# CufflessPTT-_v3.net
KiCad netlist of a schematic drawn in EAGLE
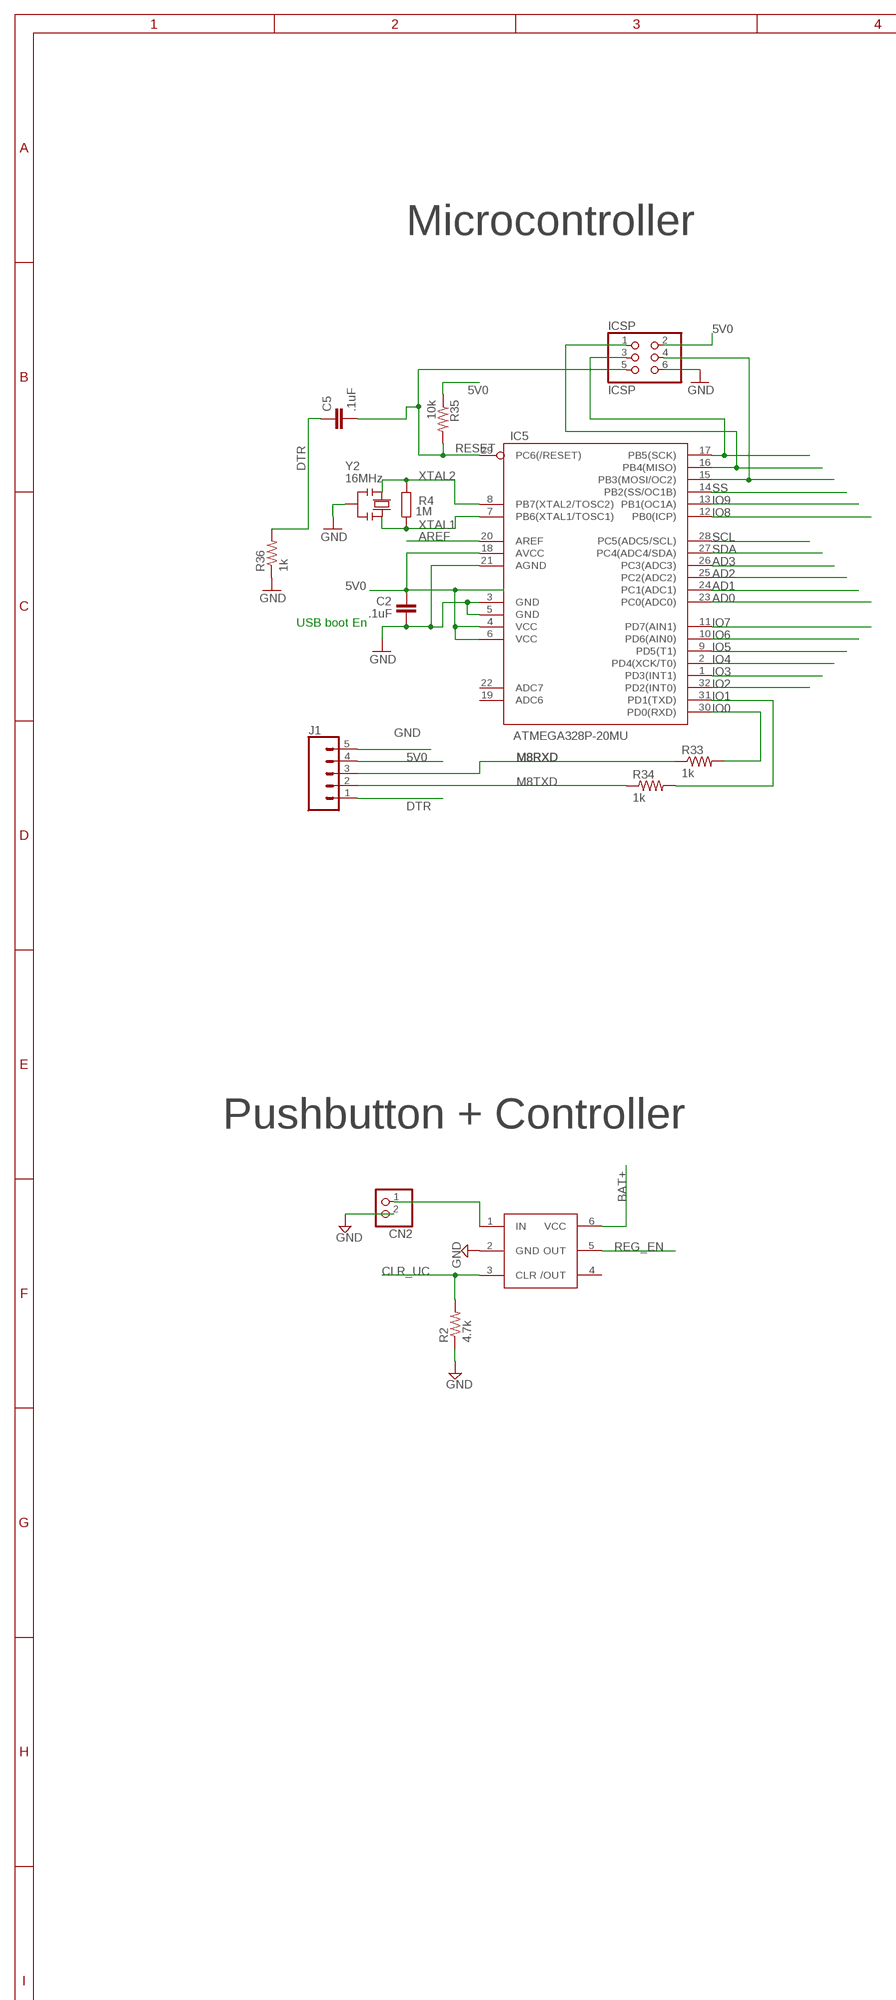
[diagram p0: schematic, sheet 1, part 1 of 2]
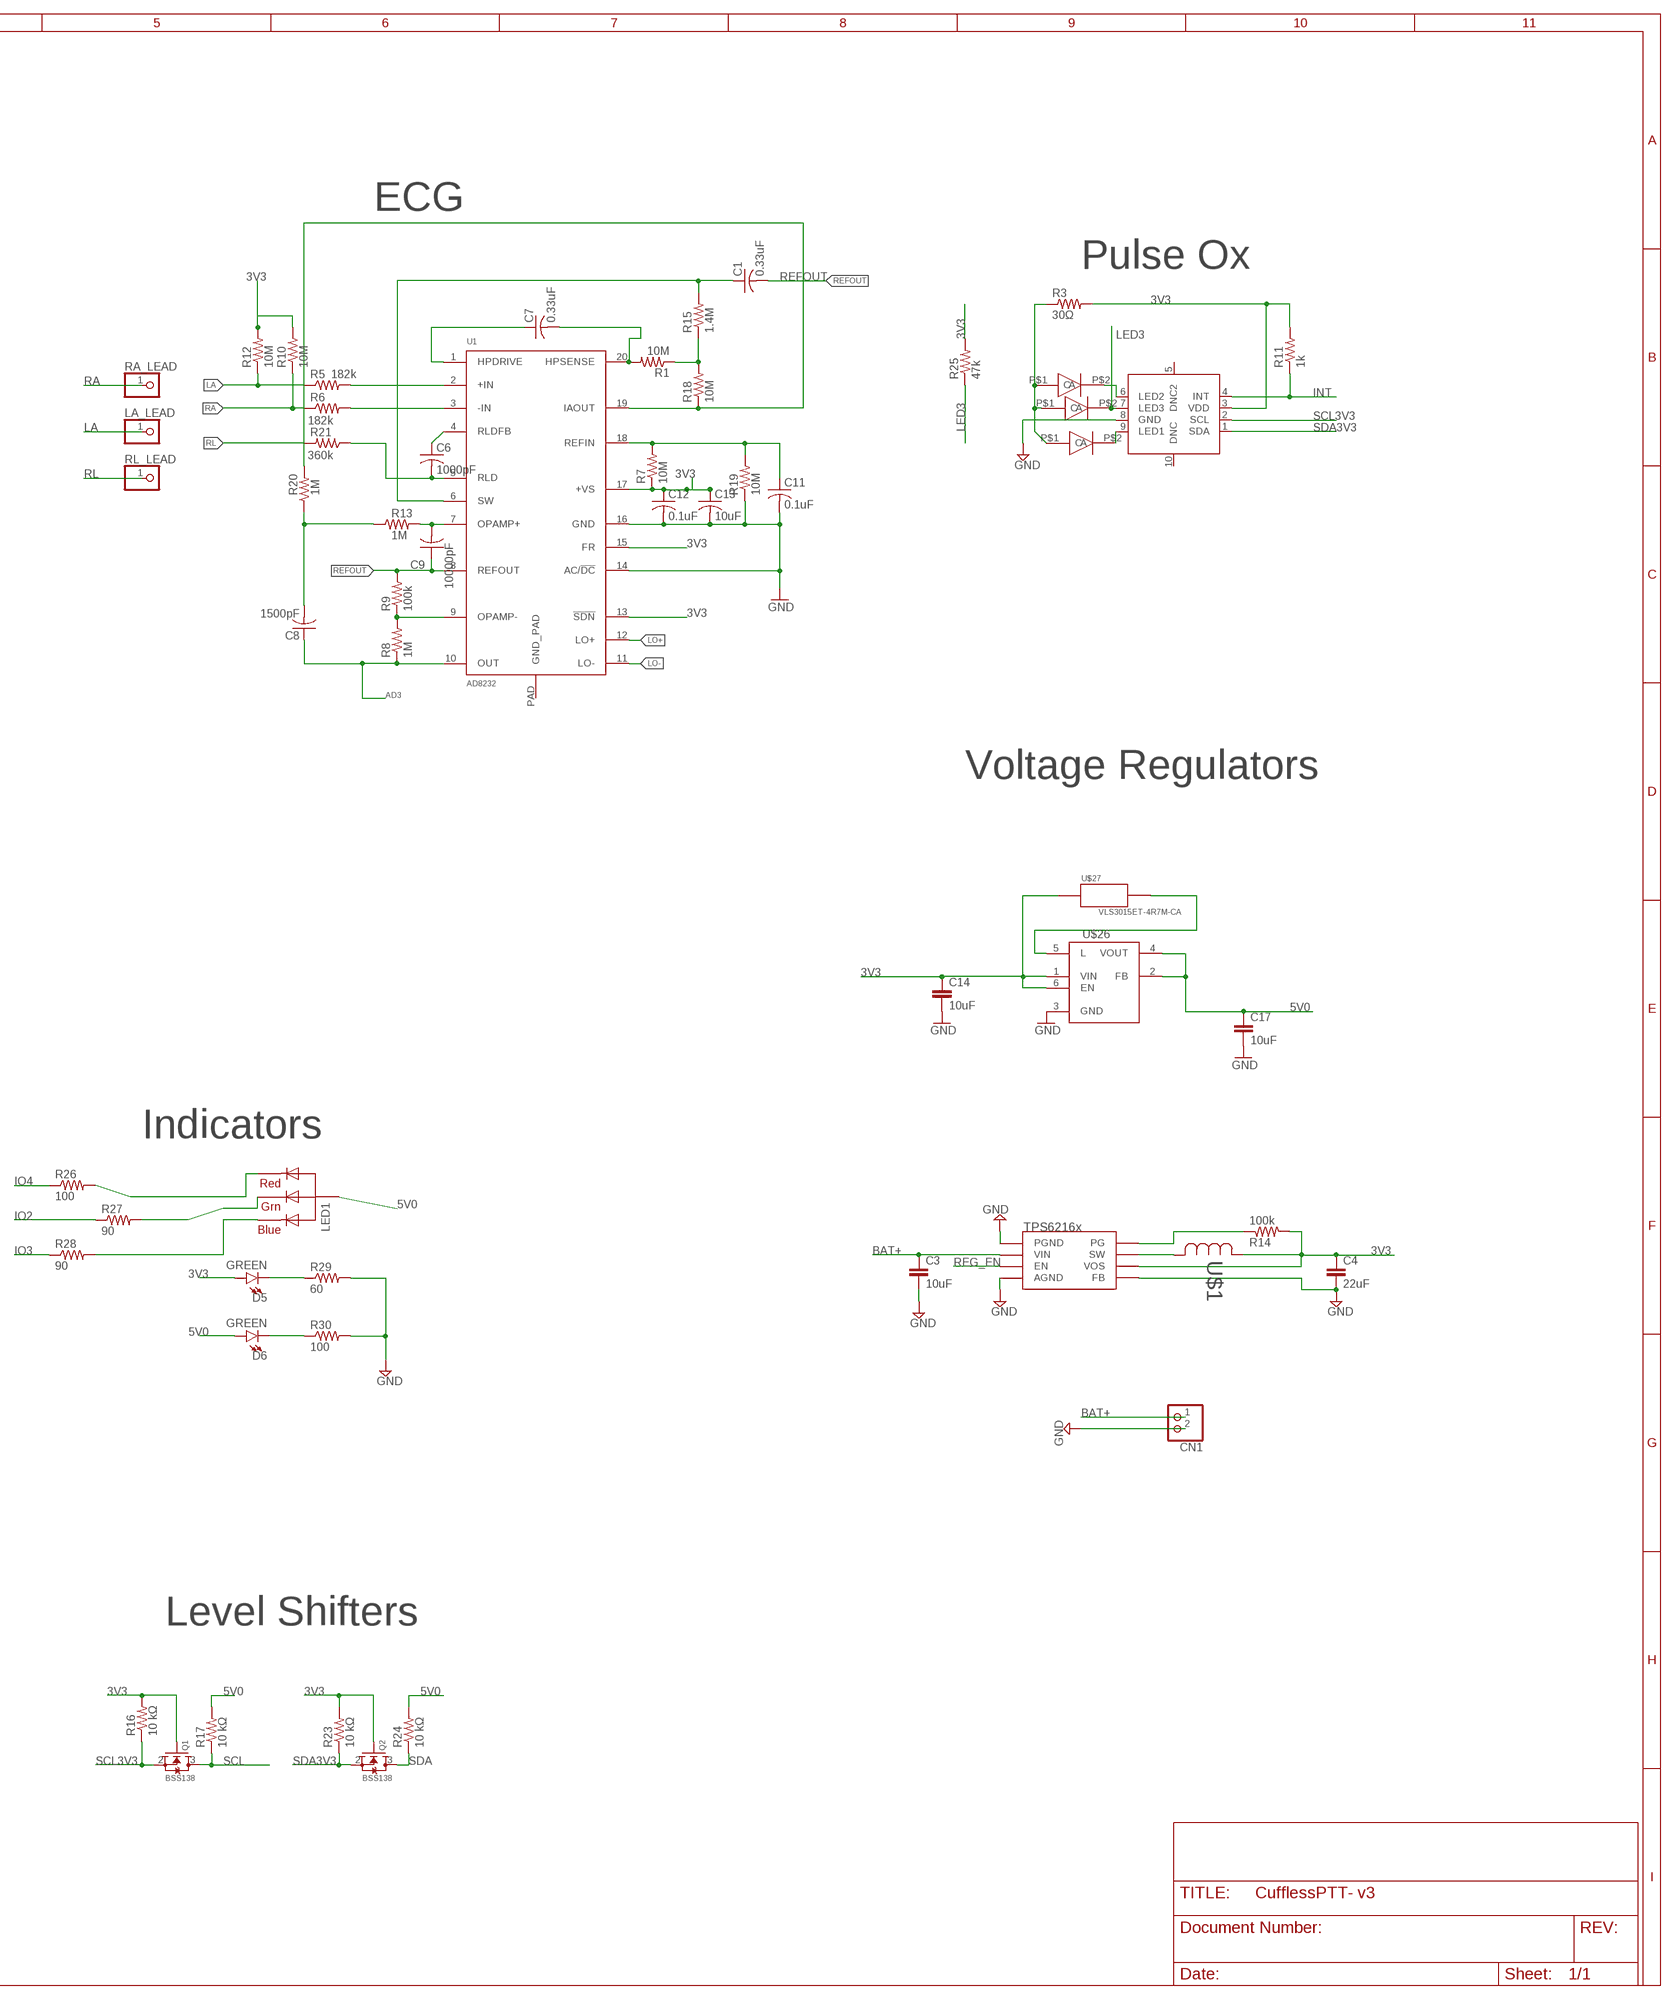
[diagram p1: schematic, sheet 1, part 2 of 2]

(export (version "E")
  (design (tool "Eeschema 10.0.6"))
  (components
    (comp (ref "C1")
      (value "0.33uF")
      (footprint "eagle-import:C0603")
      (libsource (lib "eagle-import") (part "C-USC0603"))
    )
    (comp (ref "C2")
      (value ".1uF")
      (footprint "eagle-import:C0603-ROUND")
      (libsource (lib "eagle-import") (part "C-EU0603-RND"))
    )
    (comp (ref "C3")
      (value "10uF")
      (footprint "eagle-import:C0603")
      (fields (field (name "MPN") "MCNP16V105M5X11"))
      (libsource (lib "eagle-import") (part "rcl_334_C-EUC0603"))
    )
    (comp (ref "C4")
      (value "22uF")
      (footprint "eagle-import:C0805")
      (libsource (lib "eagle-import") (part "rcl_334_C-EUC0805"))
    )
    (comp (ref "C5")
      (value ".1uF")
      (footprint "eagle-import:C0603-ROUND")
      (libsource (lib "eagle-import") (part "C-EU0603-RND"))
    )
    (comp (ref "C6")
      (value "1000pF")
      (footprint "eagle-import:C0603")
      (libsource (lib "eagle-import") (part "C-USC0603"))
    )
    (comp (ref "C7")
      (value "0.33uF")
      (footprint "eagle-import:C0603")
      (libsource (lib "eagle-import") (part "C-USC0603"))
    )
    (comp (ref "C8")
      (value "1500pF")
      (footprint "eagle-import:C0603")
      (libsource (lib "eagle-import") (part "C-USC0603"))
    )
    (comp (ref "C9")
      (value "10000pF")
      (footprint "eagle-import:C0603")
      (libsource (lib "eagle-import") (part "C-USC0603"))
    )
    (comp (ref "C11")
      (value "0.1uF")
      (footprint "eagle-import:C0603")
      (libsource (lib "eagle-import") (part "C-USC0603"))
    )
    (comp (ref "C12")
      (value "0.1uF")
      (footprint "eagle-import:C0603")
      (libsource (lib "eagle-import") (part "C-USC0603"))
    )
    (comp (ref "C13")
      (value "10uF")
      (footprint "eagle-import:C0603")
      (libsource (lib "eagle-import") (part "C-USC0603"))
    )
    (comp (ref "C14")
      (value "10uF")
      (footprint "eagle-import:C0603")
      (fields (field (name "MPN") "MCNP16V105M5X11"))
      (libsource (lib "eagle-import") (part "rcl_334_C-EUC0603"))
    )
    (comp (ref "C17")
      (value "10uF")
      (footprint "eagle-import:C0603")
      (fields (field (name "MPN") "MCNP16V105M5X11"))
      (libsource (lib "eagle-import") (part "rcl_334_C-EUC0603"))
    )
    (comp (ref "CN1")
      (value "JST_2PIN-THM")
      (footprint "eagle-import:JST-PH-2-THM")
      (libsource (lib "eagle-import") (part "JST_2PIN-THM"))
    )
    (comp (ref "CN2")
      (value "JST_2PIN-THM")
      (footprint "eagle-import:JST-PH-2-THM")
      (libsource (lib "eagle-import") (part "JST_2PIN-THM"))
    )
    (comp (ref "D5")
      (value "GREEN")
      (footprint "eagle-import:LED-0603")
      (libsource (lib "eagle-import") (part "LED-GREEN0603"))
    )
    (comp (ref "D6")
      (value "GREEN")
      (footprint "eagle-import:LED-0603")
      (libsource (lib "eagle-import") (part "LED-GREEN0603"))
    )
    (comp (ref "IC5")
      (value "ATMEGA328P-20MU")
      (footprint "eagle-import:MLF32")
      (libsource (lib "eagle-import") (part "MEGA8-MI"))
    )
    (comp (ref "ICSP")
      (value "ICSP")
      (footprint "eagle-import:2X03")
      (libsource (lib "eagle-import") (part "PINHD-2X3"))
    )
    (comp (ref "J1")
      (value "CONN_05")
      (footprint "eagle-import:1X05")
      (libsource (lib "eagle-import") (part "CONN_05"))
    )
    (comp (ref "LA_LEAD")
      (value "PINHD-1X1")
      (footprint "eagle-import:1X01")
      (libsource (lib "eagle-import") (part "PINHD-1X1"))
    )
    (comp (ref "LED1")
      (value "RGBLED_CA-5MM")
      (footprint "eagle-import:LED5MMRGB")
      (libsource (lib "eagle-import") (part "RGBLED_CA-5MM"))
    )
    (comp (ref "LED2")
      (value "SMD_COMBO")
      (footprint "eagle-import:SMD_COMBO")
      (libsource (lib "eagle-import") (part "SMD_COMBO"))
    )
    (comp (ref "LED3")
      (value "SMD_COMBO")
      (footprint "eagle-import:SMD_COMBO")
      (libsource (lib "eagle-import") (part "SMD_COMBO"))
    )
    (comp (ref "LED4")
      (value "SMD_COMBO")
      (footprint "eagle-import:SMD_COMBO")
      (libsource (lib "eagle-import") (part "SMD_COMBO"))
    )
    (comp (ref "Q1")
      (value "BSS138")
      (footprint "eagle-import:SOT23-3")
      (libsource (lib "eagle-import") (part "BSS138"))
    )
    (comp (ref "Q2")
      (value "BSS138")
      (footprint "eagle-import:SOT23-3")
      (libsource (lib "eagle-import") (part "BSS138"))
    )
    (comp (ref "R1")
      (value "10M")
      (footprint "eagle-import:0603-RES")
      (libsource (lib "eagle-import") (part "RESISTOR0603-RES"))
    )
    (comp (ref "R2")
      (value "4.7k")
      (footprint "eagle-import:R0402")
      (libsource (lib "eagle-import") (part "R-US_R0402"))
    )
    (comp (ref "R3")
      (value "30Ω")
      (footprint "eagle-import:R0402")
      (libsource (lib "eagle-import") (part "R-US_R0402"))
    )
    (comp (ref "R4")
      (value "1M")
      (footprint "eagle-import:R0603-ROUND")
      (libsource (lib "eagle-import") (part "R-EU_R0603"))
    )
    (comp (ref "R5")
      (value "182k")
      (footprint "eagle-import:0603-RES")
      (libsource (lib "eagle-import") (part "RESISTOR0603-RES"))
    )
    (comp (ref "R6")
      (value "182k")
      (footprint "eagle-import:0603-RES")
      (libsource (lib "eagle-import") (part "RESISTOR0603-RES"))
    )
    (comp (ref "R7")
      (value "10M")
      (footprint "eagle-import:0603-RES")
      (libsource (lib "eagle-import") (part "RESISTOR0603-RES"))
    )
    (comp (ref "R8")
      (value "1M")
      (footprint "eagle-import:0603-RES")
      (libsource (lib "eagle-import") (part "RESISTOR0603-RES"))
    )
    (comp (ref "R9")
      (value "100k")
      (footprint "eagle-import:0603-RES")
      (libsource (lib "eagle-import") (part "RESISTOR0603-RES"))
    )
    (comp (ref "R10")
      (value "10M")
      (footprint "eagle-import:0603-RES")
      (libsource (lib "eagle-import") (part "RESISTOR0603-RES"))
    )
    (comp (ref "R11")
      (value "1k")
      (footprint "eagle-import:R0402")
      (libsource (lib "eagle-import") (part "R-US_R0402"))
    )
    (comp (ref "R12")
      (value "10M")
      (footprint "eagle-import:0603-RES")
      (libsource (lib "eagle-import") (part "RESISTOR0603-RES"))
    )
    (comp (ref "R13")
      (value "1M")
      (footprint "eagle-import:0603-RES")
      (libsource (lib "eagle-import") (part "RESISTOR0603-RES"))
    )
    (comp (ref "R14")
      (value "100k")
      (footprint "eagle-import:R0402")
      (libsource (lib "eagle-import") (part "rcl_334_R-US_R0402"))
    )
    (comp (ref "R15")
      (value "1.4M")
      (footprint "eagle-import:0603-RES")
      (libsource (lib "eagle-import") (part "RESISTOR0603-RES"))
    )
    (comp (ref "R16")
      (value "10 kΩ")
      (footprint "eagle-import:R0402")
      (libsource (lib "eagle-import") (part "rcl_334_R-US_R0402"))
    )
    (comp (ref "R17")
      (value "10 kΩ")
      (footprint "eagle-import:R0402")
      (libsource (lib "eagle-import") (part "rcl_334_R-US_R0402"))
    )
    (comp (ref "R18")
      (value "10M")
      (footprint "eagle-import:0603-RES")
      (libsource (lib "eagle-import") (part "RESISTOR0603-RES"))
    )
    (comp (ref "R19")
      (value "10M")
      (footprint "eagle-import:0603-RES")
      (libsource (lib "eagle-import") (part "RESISTOR0603-RES"))
    )
    (comp (ref "R20")
      (value "1M")
      (footprint "eagle-import:0603-RES")
      (libsource (lib "eagle-import") (part "RESISTOR0603-RES"))
    )
    (comp (ref "R21")
      (value "360k")
      (footprint "eagle-import:0603-RES")
      (libsource (lib "eagle-import") (part "RESISTOR0603-RES"))
    )
    (comp (ref "R23")
      (value "10 kΩ")
      (footprint "eagle-import:R0402")
      (libsource (lib "eagle-import") (part "rcl_334_R-US_R0402"))
    )
    (comp (ref "R24")
      (value "10 kΩ")
      (footprint "eagle-import:R0402")
      (libsource (lib "eagle-import") (part "rcl_334_R-US_R0402"))
    )
    (comp (ref "R25")
      (value "47k")
      (footprint "eagle-import:R0402")
      (libsource (lib "eagle-import") (part "R-US_R0402"))
    )
    (comp (ref "R26")
      (value "100")
      (footprint "eagle-import:R0402")
      (libsource (lib "eagle-import") (part "resistor_348_R-US_R0402"))
    )
    (comp (ref "R27")
      (value "90")
      (footprint "eagle-import:R0402")
      (libsource (lib "eagle-import") (part "resistor_348_R-US_R0402"))
    )
    (comp (ref "R28")
      (value "90")
      (footprint "eagle-import:R0402")
      (libsource (lib "eagle-import") (part "resistor_348_R-US_R0402"))
    )
    (comp (ref "R29")
      (value "60")
      (footprint "eagle-import:R0402")
      (libsource (lib "eagle-import") (part "resistor_348_R-US_R0402"))
    )
    (comp (ref "R30")
      (value "100")
      (footprint "eagle-import:R0402")
      (libsource (lib "eagle-import") (part "resistor_348_R-US_R0402"))
    )
    (comp (ref "R33")
      (value "1k")
      (footprint "eagle-import:R0402")
      (libsource (lib "eagle-import") (part "rcl_334_R-US_R0402"))
    )
    (comp (ref "R34")
      (value "1k")
      (footprint "eagle-import:R0402")
      (libsource (lib "eagle-import") (part "rcl_334_R-US_R0402"))
    )
    (comp (ref "R35")
      (value "10k")
      (footprint "eagle-import:R0402")
      (libsource (lib "eagle-import") (part "rcl_334_R-US_R0402"))
    )
    (comp (ref "R36")
      (value "1k")
      (footprint "eagle-import:R0402")
      (libsource (lib "eagle-import") (part "rcl_334_R-US_R0402"))
    )
    (comp (ref "RA_LEAD")
      (value "PINHD-1X1")
      (footprint "eagle-import:1X01")
      (libsource (lib "eagle-import") (part "PINHD-1X1"))
    )
    (comp (ref "RL_LEAD")
      (value "PINHD-1X1")
      (footprint "eagle-import:1X01")
      (libsource (lib "eagle-import") (part "PINHD-1X1"))
    )
    (comp (ref "U$1")
      (value "VLF3012ST-2R2M1R4")
      (footprint "eagle-import:IND_3010")
      (libsource (lib "eagle-import") (part "VLF3012ST-2R2M1R4"))
    )
    (comp (ref "U$4")
      (value "SI1143")
      (footprint "eagle-import:QFN-10")
      (libsource (lib "eagle-import") (part "SI1143"))
    )
    (comp (ref "U$5")
      (value "TPS6216X")
      (footprint "eagle-import:8WSON")
      (libsource (lib "eagle-import") (part "TPS6216X"))
    )
    (comp (ref "U$15")
      (value "MAX16054")
      (footprint "eagle-import:TSOT23-6")
      (libsource (lib "eagle-import") (part "MAX16054"))
    )
    (comp (ref "U$26")
      (value "TPS61222")
      (footprint "eagle-import:SOT363_6SOIC")
      (libsource (lib "eagle-import") (part "TPS61222"))
    )
    (comp (ref "U$27")
      (value "VLS3015ET-4R7M-CA")
      (footprint "eagle-import:VLS3015ET-4R7M-CA")
      (libsource (lib "eagle-import") (part "VLS3015ET-4R7M-CA"))
    )
    (comp (ref "U1")
      (value "AD8232")
      (footprint "eagle-import:LFCSP_20")
      (libsource (lib "eagle-import") (part "AD8232"))
    )
    (comp (ref "Y2")
      (value "16MHz")
      (footprint "eagle-import:RESONATOR")
      (libsource (lib "eagle-import") (part "RESONATORMU"))
    )
  )
  (nets
    (net (code "1") (name "/3V3") (class "Default")
      (node (ref "C12") (pin "1") (pinfunction "1_1") (pintype "passive"))
      (node (ref "C13") (pin "1") (pinfunction "1_1") (pintype "passive"))
      (node (ref "C14") (pin "1") (pinfunction "1_1") (pintype "passive"))
      (node (ref "C4") (pin "1") (pinfunction "1_1") (pintype "passive"))
      (node (ref "D5") (pin "A") (pinfunction "A_A") (pintype "passive"))
      (node (ref "Q1") (pin "1") (pinfunction "G_1") (pintype "bidirectional"))
      (node (ref "Q2") (pin "1") (pinfunction "G_1") (pintype "bidirectional"))
      (node (ref "R10") (pin "2") (pinfunction "2_2") (pintype "passive"))
      (node (ref "R11") (pin "2") (pinfunction "2_2") (pintype "passive"))
      (node (ref "R12") (pin "2") (pinfunction "2_2") (pintype "passive"))
      (node (ref "R14") (pin "2") (pinfunction "2_2") (pintype "passive"))
      (node (ref "R16") (pin "2") (pinfunction "2_2") (pintype "passive"))
      (node (ref "R23") (pin "2") (pinfunction "2_2") (pintype "passive"))
      (node (ref "R25") (pin "2") (pinfunction "2_2") (pintype "passive"))
      (node (ref "R3") (pin "2") (pinfunction "2_2") (pintype "passive"))
      (node (ref "R7") (pin "1") (pinfunction "1_1") (pintype "passive"))
      (node (ref "U$1") (pin "1") (pinfunction "1_1") (pintype "passive"))
      (node (ref "U$26") (pin "1") (pinfunction "VIN_1") (pintype "bidirectional"))
      (node (ref "U$26") (pin "6") (pinfunction "EN_6") (pintype "bidirectional"))
      (node (ref "U$27") (pin "1") (pinfunction "P$1_1") (pintype "bidirectional"))
      (node (ref "U$4") (pin "3") (pinfunction "VDD_3") (pintype "bidirectional"))
      (node (ref "U$5") (pin "P$6") (pinfunction "VOS_P$6") (pintype "bidirectional"))
      (node (ref "U1") (pin "13") (pinfunction "~{SDN}_13") (pintype "bidirectional"))
      (node (ref "U1") (pin "15") (pinfunction "FR_15") (pintype "bidirectional"))
      (node (ref "U1") (pin "17") (pinfunction "+VS_17") (pintype "bidirectional"))
    )
    (net (code "2") (name "/5V0") (class "Default")
      (node (ref "C17") (pin "1") (pinfunction "1_1") (pintype "passive"))
      (node (ref "C2") (pin "2") (pinfunction "2_2") (pintype "passive"))
      (node (ref "D6") (pin "A") (pinfunction "A_A") (pintype "passive"))
      (node (ref "IC5") (pin "18") (pinfunction "AVCC_18") (pintype "bidirectional"))
      (node (ref "IC5") (pin "4") (pinfunction "VCC_4") (pintype "bidirectional"))
      (node (ref "IC5") (pin "6") (pinfunction "VCC_6") (pintype "bidirectional"))
      (node (ref "ICSP") (pin "2") (pinfunction "2_2") (pintype "passive"))
      (node (ref "J1") (pin "4") (pinfunction "4_4") (pintype "passive"))
      (node (ref "LED1") (pin "2") (pinfunction "VCC_2") (pintype "bidirectional"))
      (node (ref "R17") (pin "2") (pinfunction "2_2") (pintype "passive"))
      (node (ref "R24") (pin "2") (pinfunction "2_2") (pintype "passive"))
      (node (ref "R35") (pin "1") (pinfunction "1_1") (pintype "passive"))
      (node (ref "U$26") (pin "2") (pinfunction "FB_2") (pintype "bidirectional"))
      (node (ref "U$26") (pin "4") (pinfunction "VOUT_4") (pintype "bidirectional"))
    )
    (net (code "3") (name "/AD0") (class "Default")
      (node (ref "IC5") (pin "23") (pinfunction "PC0(ADC0)_23") (pintype "bidirectional"))
    )
    (net (code "4") (name "/AD1") (class "Default")
      (node (ref "IC5") (pin "24") (pinfunction "PC1(ADC1)_24") (pintype "bidirectional"))
    )
    (net (code "5") (name "/AD2") (class "Default")
      (node (ref "IC5") (pin "25") (pinfunction "PC2(ADC2)_25") (pintype "bidirectional"))
    )
    (net (code "6") (name "/AD3") (class "Default")
      (node (ref "C8") (pin "1") (pinfunction "1_1") (pintype "passive"))
      (node (ref "IC5") (pin "26") (pinfunction "PC3(ADC3)_26") (pintype "bidirectional"))
      (node (ref "R8") (pin "1") (pinfunction "1_1") (pintype "passive"))
      (node (ref "U1") (pin "10") (pinfunction "OUT_10") (pintype "bidirectional"))
    )
    (net (code "7") (name "/AREF") (class "Default")
      (node (ref "IC5") (pin "20") (pinfunction "AREF_20") (pintype "bidirectional"))
    )
    (net (code "8") (name "/BAT+") (class "Default")
      (node (ref "C3") (pin "1") (pinfunction "1_1") (pintype "passive"))
      (node (ref "CN1") (pin "1") (pinfunction "2_1") (pintype "passive"))
      (node (ref "U$15") (pin "6") (pinfunction "VCC_6") (pintype "bidirectional"))
      (node (ref "U$5") (pin "P$2") (pinfunction "VIN_P$2") (pintype "bidirectional"))
    )
    (net (code "9") (name "/CLR_UC") (class "Default")
      (node (ref "R2") (pin "2") (pinfunction "2_2") (pintype "passive"))
      (node (ref "U$15") (pin "3") (pinfunction "CLR_3") (pintype "bidirectional"))
    )
    (net (code "10") (name "/DTR") (class "Default")
      (node (ref "C5") (pin "1") (pinfunction "1_1") (pintype "passive"))
      (node (ref "J1") (pin "1") (pinfunction "1_1") (pintype "passive"))
      (node (ref "R36") (pin "2") (pinfunction "2_2") (pintype "passive"))
    )
    (net (code "11") (name "/INT") (class "Default")
      (node (ref "R11") (pin "1") (pinfunction "1_1") (pintype "passive"))
      (node (ref "U$4") (pin "4") (pinfunction "INT_4") (pintype "bidirectional"))
    )
    (net (code "12") (name "/IO0") (class "Default")
      (node (ref "IC5") (pin "30") (pinfunction "PD0(RXD)_30") (pintype "bidirectional"))
      (node (ref "R33") (pin "2") (pinfunction "2_2") (pintype "passive"))
    )
    (net (code "13") (name "/IO1") (class "Default")
      (node (ref "IC5") (pin "31") (pinfunction "PD1(TXD)_31") (pintype "bidirectional"))
      (node (ref "R34") (pin "2") (pinfunction "2_2") (pintype "passive"))
    )
    (net (code "14") (name "/IO2") (class "Default")
      (node (ref "IC5") (pin "32") (pinfunction "PD2(INT0)_32") (pintype "bidirectional"))
      (node (ref "R27") (pin "1") (pinfunction "1_1") (pintype "passive"))
    )
    (net (code "15") (name "/IO3") (class "Default")
      (node (ref "IC5") (pin "1") (pinfunction "PD3(INT1)_1") (pintype "bidirectional"))
      (node (ref "R28") (pin "1") (pinfunction "1_1") (pintype "passive"))
    )
    (net (code "16") (name "/IO4") (class "Default")
      (node (ref "IC5") (pin "2") (pinfunction "PD4(XCK/T0)_2") (pintype "bidirectional"))
      (node (ref "R26") (pin "1") (pinfunction "1_1") (pintype "passive"))
    )
    (net (code "17") (name "/IO5") (class "Default")
      (node (ref "IC5") (pin "9") (pinfunction "PD5(T1)_9") (pintype "bidirectional"))
    )
    (net (code "18") (name "/IO6") (class "Default")
      (node (ref "IC5") (pin "10") (pinfunction "PD6(AIN0)_10") (pintype "bidirectional"))
    )
    (net (code "19") (name "/IO7") (class "Default")
      (node (ref "IC5") (pin "11") (pinfunction "PD7(AIN1)_11") (pintype "bidirectional"))
    )
    (net (code "20") (name "/IO8") (class "Default")
      (node (ref "IC5") (pin "12") (pinfunction "PB0(ICP)_12") (pintype "bidirectional"))
    )
    (net (code "21") (name "/IO9") (class "Default")
      (node (ref "IC5") (pin "13") (pinfunction "PB1(OC1A)_13") (pintype "bidirectional"))
    )
    (net (code "22") (name "/LED3") (class "Default")
      (node (ref "LED2") (pin "P$2") (pinfunction "C_P$2") (pintype "bidirectional"))
      (node (ref "R25") (pin "1") (pinfunction "1_1") (pintype "passive"))
      (node (ref "U$4") (pin "7") (pinfunction "LED3_7") (pintype "bidirectional"))
    )
    (net (code "23") (name "/M8RXD") (class "Default")
      (node (ref "J1") (pin "3") (pinfunction "3_3") (pintype "passive"))
      (node (ref "R33") (pin "1") (pinfunction "1_1") (pintype "passive"))
    )
    (net (code "24") (name "/M8TXD") (class "Default")
      (node (ref "J1") (pin "2") (pinfunction "2_2") (pintype "passive"))
      (node (ref "R34") (pin "1") (pinfunction "1_1") (pintype "passive"))
    )
    (net (code "25") (name "/REG_EN") (class "Default")
      (node (ref "U$15") (pin "5") (pinfunction "OUT_5") (pintype "bidirectional"))
      (node (ref "U$5") (pin "P$3") (pinfunction "EN_P$3") (pintype "bidirectional"))
    )
    (net (code "26") (name "/RESET") (class "Default")
      (node (ref "C5") (pin "2") (pinfunction "2_2") (pintype "passive"))
      (node (ref "IC5") (pin "29") (pinfunction "PC6(/RESET)_29") (pintype "bidirectional"))
      (node (ref "ICSP") (pin "5") (pinfunction "5_5") (pintype "passive"))
      (node (ref "R35") (pin "2") (pinfunction "2_2") (pintype "passive"))
    )
    (net (code "27") (name "/SCL") (class "Default")
      (node (ref "IC5") (pin "28") (pinfunction "PC5(ADC5/SCL)_28") (pintype "bidirectional"))
      (node (ref "Q1") (pin "3") (pinfunction "D_3") (pintype "bidirectional"))
      (node (ref "R17") (pin "1") (pinfunction "1_1") (pintype "passive"))
    )
    (net (code "28") (name "/SCL3V3") (class "Default")
      (node (ref "Q1") (pin "2") (pinfunction "S_2") (pintype "bidirectional"))
      (node (ref "R16") (pin "1") (pinfunction "1_1") (pintype "passive"))
      (node (ref "U$4") (pin "2") (pinfunction "SCL_2") (pintype "bidirectional"))
    )
    (net (code "29") (name "/SDA") (class "Default")
      (node (ref "IC5") (pin "27") (pinfunction "PC4(ADC4/SDA)_27") (pintype "bidirectional"))
      (node (ref "Q2") (pin "3") (pinfunction "D_3") (pintype "bidirectional"))
      (node (ref "R24") (pin "1") (pinfunction "1_1") (pintype "passive"))
    )
    (net (code "30") (name "/SDA3V3") (class "Default")
      (node (ref "Q2") (pin "2") (pinfunction "S_2") (pintype "bidirectional"))
      (node (ref "R23") (pin "1") (pinfunction "1_1") (pintype "passive"))
      (node (ref "U$4") (pin "1") (pinfunction "SDA_1") (pintype "bidirectional"))
    )
    (net (code "31") (name "/SS") (class "Default")
      (node (ref "IC5") (pin "14") (pinfunction "PB2(SS/OC1B)_14") (pintype "bidirectional"))
    )
    (net (code "32") (name "/XTAL1") (class "Default")
      (node (ref "IC5") (pin "7") (pinfunction "PB6(XTAL1/TOSC1)_7") (pintype "bidirectional"))
      (node (ref "R4") (pin "1") (pinfunction "1_1") (pintype "passive"))
      (node (ref "Y2") (pin "3") (pinfunction "3_3") (pintype "passive"))
    )
    (net (code "33") (name "/XTAL2") (class "Default")
      (node (ref "IC5") (pin "8") (pinfunction "PB7(XTAL2/TOSC2)_8") (pintype "bidirectional"))
      (node (ref "R4") (pin "2") (pinfunction "2_2") (pintype "passive"))
      (node (ref "Y2") (pin "1") (pinfunction "1_1") (pintype "passive"))
    )
    (net (code "34") (name "GND") (class "Default")
      (node (ref "C11") (pin "2") (pinfunction "2_2") (pintype "passive"))
      (node (ref "C12") (pin "2") (pinfunction "2_2") (pintype "passive"))
      (node (ref "C13") (pin "2") (pinfunction "2_2") (pintype "passive"))
      (node (ref "C14") (pin "2") (pinfunction "2_2") (pintype "passive"))
      (node (ref "C17") (pin "2") (pinfunction "2_2") (pintype "passive"))
      (node (ref "C2") (pin "1") (pinfunction "1_1") (pintype "passive"))
      (node (ref "C3") (pin "2") (pinfunction "2_2") (pintype "passive"))
      (node (ref "C4") (pin "2") (pinfunction "2_2") (pintype "passive"))
      (node (ref "CN1") (pin "2") (pinfunction "1_2") (pintype "passive"))
      (node (ref "CN2") (pin "2") (pinfunction "1_2") (pintype "passive"))
      (node (ref "IC5") (pin "21") (pinfunction "AGND_21") (pintype "bidirectional"))
      (node (ref "IC5") (pin "3") (pinfunction "GND_3") (pintype "bidirectional"))
      (node (ref "IC5") (pin "5") (pinfunction "GND_5") (pintype "bidirectional"))
      (node (ref "ICSP") (pin "6") (pinfunction "6_6") (pintype "passive"))
      (node (ref "J1") (pin "5") (pinfunction "5_5") (pintype "passive"))
      (node (ref "R19") (pin "1") (pinfunction "1_1") (pintype "passive"))
      (node (ref "R2") (pin "1") (pinfunction "1_1") (pintype "passive"))
      (node (ref "R29") (pin "2") (pinfunction "2_2") (pintype "passive"))
      (node (ref "R30") (pin "2") (pinfunction "2_2") (pintype "passive"))
      (node (ref "R36") (pin "1") (pinfunction "1_1") (pintype "passive"))
      (node (ref "U$15") (pin "2") (pinfunction "GND_2") (pintype "bidirectional"))
      (node (ref "U$26") (pin "3") (pinfunction "GND_3") (pintype "bidirectional"))
      (node (ref "U$4") (pin "8") (pinfunction "GND_8") (pintype "bidirectional"))
      (node (ref "U$5") (pin "P$1") (pinfunction "PGND_P$1") (pintype "bidirectional"))
      (node (ref "U$5") (pin "P$4") (pinfunction "AGND_P$4") (pintype "bidirectional"))
      (node (ref "U$5") (pin "P$5") (pinfunction "FB_P$5") (pintype "bidirectional"))
      (node (ref "U$5") (pin "P$9") (pinfunction "AGND_P$9") (pintype "bidirectional"))
      (node (ref "U1") (pin "14") (pinfunction "AC/~{DC}_14") (pintype "bidirectional"))
      (node (ref "U1") (pin "16") (pinfunction "GND_16") (pintype "bidirectional"))
      (node (ref "Y2") (pin "2") (pinfunction "2_2") (pintype "passive"))
    )
    (net (code "35") (name "LA") (class "Default")
      (node (ref "LA_LEAD") (pin "1") (pinfunction "1_1") (pintype "passive"))
      (node (ref "R12") (pin "1") (pinfunction "1_1") (pintype "passive"))
      (node (ref "R5") (pin "1") (pinfunction "1_1") (pintype "passive"))
    )
    (net (code "36") (name "LO+") (class "Default")
      (node (ref "U1") (pin "12") (pinfunction "LO+_12") (pintype "bidirectional"))
    )
    (net (code "37") (name "LO-") (class "Default")
      (node (ref "U1") (pin "11") (pinfunction "LO-_11") (pintype "bidirectional"))
    )
    (net (code "38") (name "Net-(C8-Pad2)") (class "Default")
      (node (ref "C8") (pin "2") (pinfunction "2_2") (pintype "passive"))
      (node (ref "R13") (pin "1") (pinfunction "1_1") (pintype "passive"))
      (node (ref "R20") (pin "1") (pinfunction "1_1") (pintype "passive"))
    )
    (net (code "39") (name "Net-(CN2-2)") (class "Default")
      (node (ref "CN2") (pin "1") (pinfunction "2_1") (pintype "passive"))
      (node (ref "U$15") (pin "1") (pinfunction "IN_1") (pintype "bidirectional"))
    )
    (net (code "40") (name "Net-(D5-PadC)") (class "Default")
      (node (ref "D5") (pin "C") (pinfunction "C_C") (pintype "passive"))
      (node (ref "R29") (pin "1") (pinfunction "1_1") (pintype "passive"))
    )
    (net (code "41") (name "Net-(D6-PadC)") (class "Default")
      (node (ref "D6") (pin "C") (pinfunction "C_C") (pintype "passive"))
      (node (ref "R30") (pin "1") (pinfunction "1_1") (pintype "passive"))
    )
    (net (code "42") (name "Net-(IC5-PB3(MOSI{slash}OC2))") (class "Default")
      (node (ref "IC5") (pin "15") (pinfunction "PB3(MOSI/OC2)_15") (pintype "bidirectional"))
      (node (ref "ICSP") (pin "4") (pinfunction "4_4") (pintype "passive"))
    )
    (net (code "43") (name "Net-(IC5-PB4(MISO))") (class "Default")
      (node (ref "IC5") (pin "16") (pinfunction "PB4(MISO)_16") (pintype "bidirectional"))
      (node (ref "ICSP") (pin "1") (pinfunction "1_1") (pintype "passive"))
    )
    (net (code "44") (name "Net-(IC5-PB5(SCK))") (class "Default")
      (node (ref "IC5") (pin "17") (pinfunction "PB5(SCK)_17") (pintype "bidirectional"))
      (node (ref "ICSP") (pin "3") (pinfunction "3_3") (pintype "passive"))
    )
    (net (code "45") (name "Net-(LED1-BLUE)") (class "Default")
      (node (ref "LED1") (pin "4") (pinfunction "BLUE_4") (pintype "bidirectional"))
      (node (ref "R28") (pin "2") (pinfunction "2_2") (pintype "passive"))
    )
    (net (code "46") (name "Net-(LED1-GREEN)") (class "Default")
      (node (ref "LED1") (pin "3") (pinfunction "GREEN_3") (pintype "bidirectional"))
      (node (ref "R27") (pin "2") (pinfunction "2_2") (pintype "passive"))
    )
    (net (code "47") (name "Net-(LED1-RED)") (class "Default")
      (node (ref "LED1") (pin "1") (pinfunction "RED_1") (pintype "bidirectional"))
      (node (ref "R26") (pin "2") (pinfunction "2_2") (pintype "passive"))
    )
    (net (code "48") (name "Net-(LED2-A)") (class "Default")
      (node (ref "LED2") (pin "P$1") (pinfunction "A_P$1") (pintype "bidirectional"))
      (node (ref "LED3") (pin "P$1") (pinfunction "A_P$1") (pintype "bidirectional"))
      (node (ref "LED4") (pin "P$1") (pinfunction "A_P$1") (pintype "bidirectional"))
      (node (ref "R3") (pin "1") (pinfunction "1_1") (pintype "passive"))
    )
    (net (code "49") (name "Net-(LED3-C)") (class "Default")
      (node (ref "LED3") (pin "P$2") (pinfunction "C_P$2") (pintype "bidirectional"))
      (node (ref "U$4") (pin "6") (pinfunction "LED2_6") (pintype "bidirectional"))
    )
    (net (code "50") (name "Net-(LED4-C)") (class "Default")
      (node (ref "LED4") (pin "P$2") (pinfunction "C_P$2") (pintype "bidirectional"))
      (node (ref "U$4") (pin "9") (pinfunction "LED1_9") (pintype "bidirectional"))
    )
    (net (code "51") (name "Net-(R1-Pad1)") (class "Default")
      (node (ref "R1") (pin "1") (pinfunction "1_1") (pintype "passive"))
      (node (ref "R15") (pin "1") (pinfunction "1_1") (pintype "passive"))
      (node (ref "R18") (pin "2") (pinfunction "2_2") (pintype "passive"))
    )
    (net (code "52") (name "Net-(U$5-PG)") (class "Default")
      (node (ref "R14") (pin "1") (pinfunction "1_1") (pintype "passive"))
      (node (ref "U$5") (pin "P$8") (pinfunction "PG_P$8") (pintype "bidirectional"))
    )
    (net (code "53") (name "Net-(U$5-SW)") (class "Default")
      (node (ref "U$1") (pin "2") (pinfunction "2_2") (pintype "passive"))
      (node (ref "U$5") (pin "P$7") (pinfunction "SW_P$7") (pintype "bidirectional"))
    )
    (net (code "54") (name "Net-(U$26-L)") (class "Default")
      (node (ref "U$26") (pin "5") (pinfunction "L_5") (pintype "bidirectional"))
      (node (ref "U$27") (pin "2") (pinfunction "P$2_2") (pintype "bidirectional"))
    )
    (net (code "55") (name "Net-(U1-+IN)") (class "Default")
      (node (ref "R5") (pin "2") (pinfunction "2_2") (pintype "passive"))
      (node (ref "U1") (pin "2") (pinfunction "+IN_2") (pintype "bidirectional"))
    )
    (net (code "56") (name "Net-(U1--IN)") (class "Default")
      (node (ref "R6") (pin "2") (pinfunction "2_2") (pintype "passive"))
      (node (ref "U1") (pin "3") (pinfunction "-IN_3") (pintype "bidirectional"))
    )
    (net (code "57") (name "Net-(U1-HPDRIVE)") (class "Default")
      (node (ref "C7") (pin "1") (pinfunction "1_1") (pintype "passive"))
      (node (ref "U1") (pin "1") (pinfunction "HPDRIVE_1") (pintype "bidirectional"))
    )
    (net (code "58") (name "Net-(U1-HPSENSE)") (class "Default")
      (node (ref "C7") (pin "2") (pinfunction "2_2") (pintype "passive"))
      (node (ref "R1") (pin "2") (pinfunction "2_2") (pintype "passive"))
      (node (ref "U1") (pin "20") (pinfunction "HPSENSE_20") (pintype "bidirectional"))
    )
    (net (code "59") (name "Net-(U1-IAOUT)") (class "Default")
      (node (ref "R18") (pin "1") (pinfunction "1_1") (pintype "passive"))
      (node (ref "R20") (pin "2") (pinfunction "2_2") (pintype "passive"))
      (node (ref "U1") (pin "19") (pinfunction "IAOUT_19") (pintype "bidirectional"))
    )
    (net (code "60") (name "Net-(U1-OPAMP+)") (class "Default")
      (node (ref "C9") (pin "2") (pinfunction "2_2") (pintype "passive"))
      (node (ref "R13") (pin "2") (pinfunction "2_2") (pintype "passive"))
      (node (ref "U1") (pin "7") (pinfunction "OPAMP+_7") (pintype "bidirectional"))
    )
    (net (code "61") (name "Net-(U1-OPAMP-)") (class "Default")
      (node (ref "R8") (pin "2") (pinfunction "2_2") (pintype "passive"))
      (node (ref "R9") (pin "1") (pinfunction "1_1") (pintype "passive"))
      (node (ref "U1") (pin "9") (pinfunction "OPAMP-_9") (pintype "bidirectional"))
    )
    (net (code "62") (name "Net-(U1-REFIN)") (class "Default")
      (node (ref "C11") (pin "1") (pinfunction "1_1") (pintype "passive"))
      (node (ref "R19") (pin "2") (pinfunction "2_2") (pintype "passive"))
      (node (ref "R7") (pin "2") (pinfunction "2_2") (pintype "passive"))
      (node (ref "U1") (pin "18") (pinfunction "REFIN_18") (pintype "bidirectional"))
    )
    (net (code "63") (name "Net-(U1-RLD)") (class "Default")
      (node (ref "C6") (pin "2") (pinfunction "2_2") (pintype "passive"))
      (node (ref "R21") (pin "1") (pinfunction "1_1") (pintype "passive"))
      (node (ref "U1") (pin "5") (pinfunction "RLD_5") (pintype "bidirectional"))
    )
    (net (code "64") (name "Net-(U1-RLDFB)") (class "Default")
      (node (ref "C6") (pin "1") (pinfunction "1_1") (pintype "passive"))
      (node (ref "U1") (pin "4") (pinfunction "RLDFB_4") (pintype "bidirectional"))
    )
    (net (code "65") (name "Net-(U1-SW)") (class "Default")
      (node (ref "C1") (pin "1") (pinfunction "1_1") (pintype "passive"))
      (node (ref "R15") (pin "2") (pinfunction "2_2") (pintype "passive"))
      (node (ref "U1") (pin "6") (pinfunction "SW_6") (pintype "bidirectional"))
    )
    (net (code "66") (name "RA") (class "Default")
      (node (ref "R10") (pin "1") (pinfunction "1_1") (pintype "passive"))
      (node (ref "R6") (pin "1") (pinfunction "1_1") (pintype "passive"))
      (node (ref "RA_LEAD") (pin "1") (pinfunction "1_1") (pintype "passive"))
    )
    (net (code "67") (name "REFOUT") (class "Default")
      (node (ref "C1") (pin "2") (pinfunction "2_2") (pintype "passive"))
      (node (ref "C9") (pin "1") (pinfunction "1_1") (pintype "passive"))
      (node (ref "R9") (pin "2") (pinfunction "2_2") (pintype "passive"))
      (node (ref "U1") (pin "8") (pinfunction "REFOUT_8") (pintype "bidirectional"))
    )
    (net (code "68") (name "RL") (class "Default")
      (node (ref "R21") (pin "2") (pinfunction "2_2") (pintype "passive"))
      (node (ref "RL_LEAD") (pin "1") (pinfunction "1_1") (pintype "passive"))
    )
    (net (code "69") (name "unconnected-(IC5-ADC6-Pad19)") (class "Default")
      (node (ref "IC5") (pin "19") (pinfunction "ADC6_19") (pintype "bidirectional"))
    )
    (net (code "70") (name "unconnected-(IC5-ADC7-Pad22)") (class "Default")
      (node (ref "IC5") (pin "22") (pinfunction "ADC7_22") (pintype "bidirectional"))
    )
    (net (code "71") (name "unconnected-(U$4-DNC-Pad10)") (class "Default")
      (node (ref "U$4") (pin "10") (pinfunction "DNC_10") (pintype "bidirectional"))
    )
    (net (code "72") (name "unconnected-(U$4-DNC2-Pad5)") (class "Default")
      (node (ref "U$4") (pin "5") (pinfunction "DNC2_5") (pintype "bidirectional"))
    )
    (net (code "73") (name "unconnected-(U$15-{slash}OUT-Pad4)") (class "Default")
      (node (ref "U$15") (pin "4") (pinfunction "/OUT_4") (pintype "bidirectional"))
    )
    (net (code "74") (name "unconnected-(U1-GND_PAD-PadPAD)") (class "Default")
      (node (ref "U1") (pin "PAD") (pinfunction "GND_PAD_PAD") (pintype "bidirectional"))
    )
  )
)
